# hermes-control.net
KiCad netlist of a schematic drawn in EAGLE
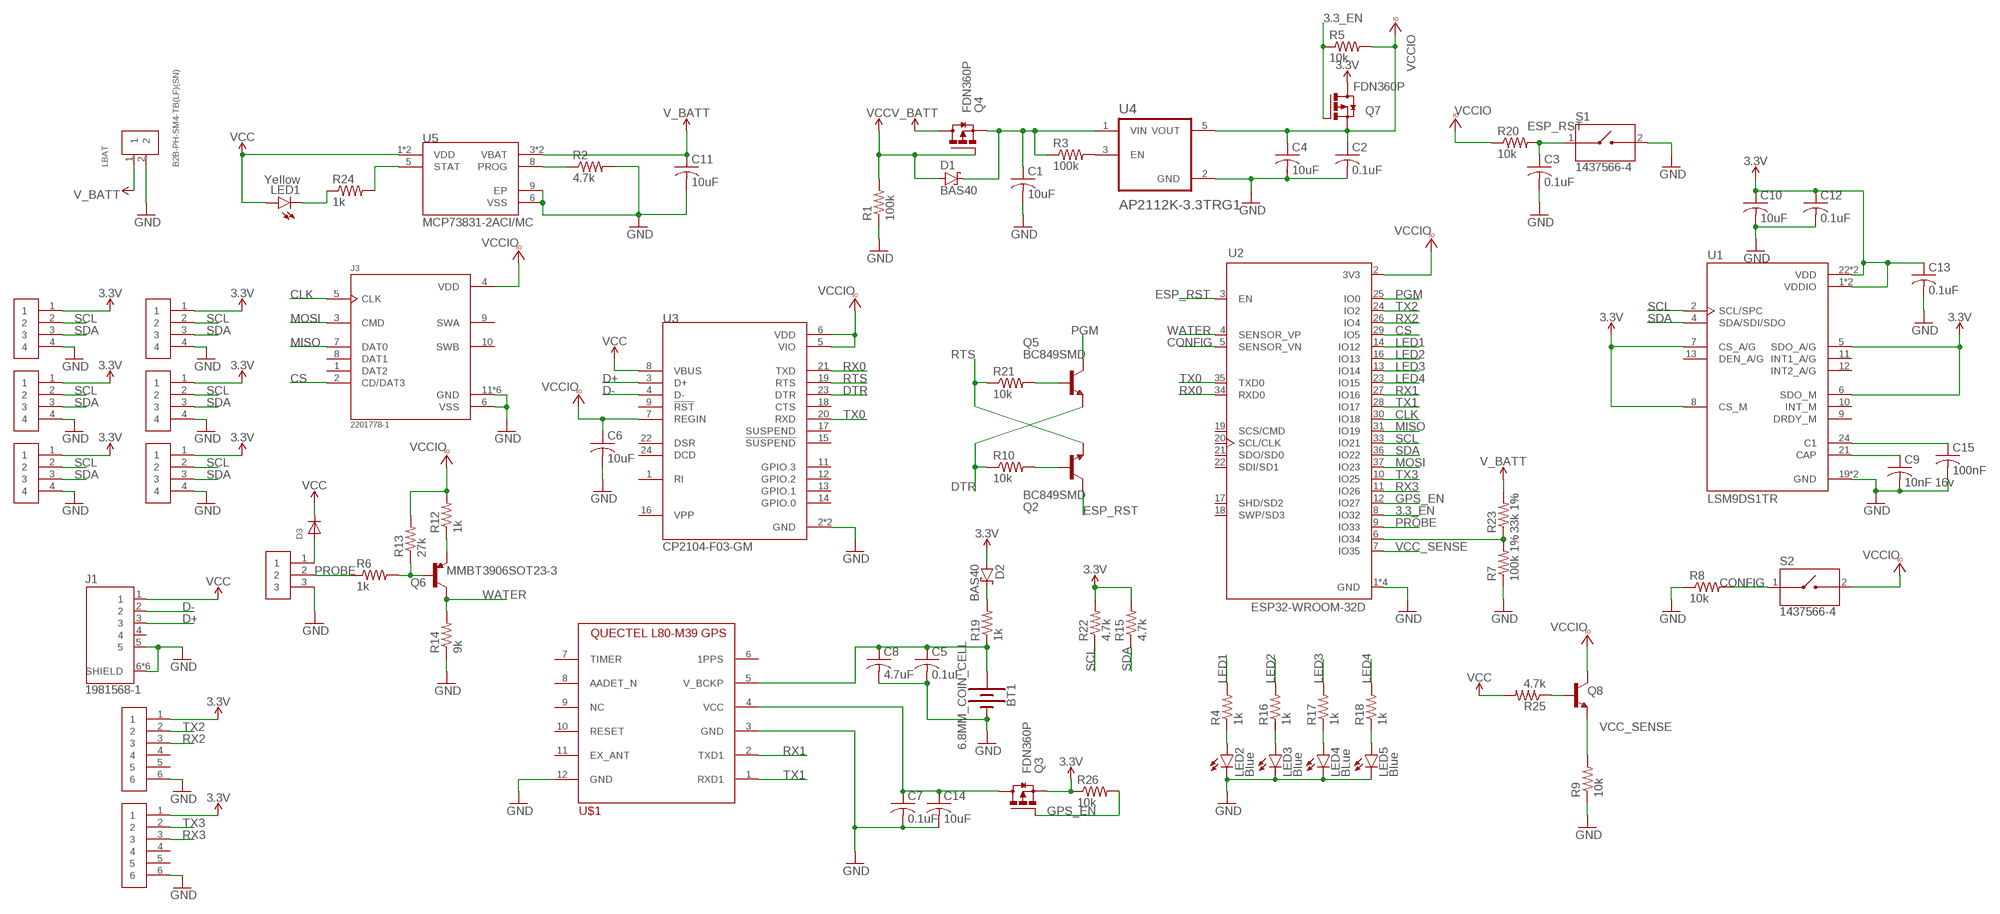
[diagram p0: schematic, sheet 1]

(export (version "E")
  (design (tool "Eeschema 10.0.6"))
  (components
    (comp (ref "BT1")
      (value "6.8MM_COIN_CELL")
      (footprint "eagle-import:BATTCON-6.8MM")
      (libsource (lib "eagle-import") (part "BATTERY-6.8MM_SMD"))
    )
    (comp (ref "C1")
      (value "10uF")
      (footprint "eagle-import:C0603")
      (libsource (lib "eagle-import") (part "C-USC0603"))
    )
    (comp (ref "C2")
      (value "0.1uF")
      (footprint "eagle-import:C0603")
      (libsource (lib "eagle-import") (part "C-USC0603"))
    )
    (comp (ref "C3")
      (value "0.1uF")
      (footprint "eagle-import:C0603")
      (libsource (lib "eagle-import") (part "C-USC0603"))
    )
    (comp (ref "C4")
      (value "10uF")
      (footprint "eagle-import:C0603")
      (libsource (lib "eagle-import") (part "C-USC0603"))
    )
    (comp (ref "C5")
      (value "0.1uF")
      (footprint "eagle-import:C0603")
      (libsource (lib "eagle-import") (part "C-USC0603"))
    )
    (comp (ref "C6")
      (value "10uF")
      (footprint "eagle-import:C0603")
      (libsource (lib "eagle-import") (part "C-USC0603"))
    )
    (comp (ref "C7")
      (value "0.1uF")
      (footprint "eagle-import:C0603")
      (libsource (lib "eagle-import") (part "C-USC0603"))
    )
    (comp (ref "C8")
      (value "4.7uF")
      (footprint "eagle-import:C0603")
      (libsource (lib "eagle-import") (part "C-USC0603"))
    )
    (comp (ref "C9")
      (value "10nF 16v")
      (footprint "eagle-import:C0603")
      (libsource (lib "eagle-import") (part "C-USC0603"))
    )
    (comp (ref "C10")
      (value "10uF")
      (footprint "eagle-import:C0603")
      (libsource (lib "eagle-import") (part "C-USC0603"))
    )
    (comp (ref "C11")
      (value "10uF")
      (footprint "eagle-import:C0603")
      (libsource (lib "eagle-import") (part "C-USC0603"))
    )
    (comp (ref "C12")
      (value "0.1uF")
      (footprint "eagle-import:C0603")
      (libsource (lib "eagle-import") (part "C-USC0603"))
    )
    (comp (ref "C13")
      (value "0.1uF")
      (footprint "eagle-import:C0603")
      (libsource (lib "eagle-import") (part "C-USC0603"))
    )
    (comp (ref "C14")
      (value "10uF")
      (footprint "eagle-import:C0603")
      (libsource (lib "eagle-import") (part "C-USC0603"))
    )
    (comp (ref "C15")
      (value "100nF")
      (footprint "eagle-import:C0603")
      (libsource (lib "eagle-import") (part "C-USC0603"))
    )
    (comp (ref "D1")
      (value "BAS40")
      (footprint "eagle-import:SOT23")
      (libsource (lib "eagle-import") (part "BAS40"))
    )
    (comp (ref "D2")
      (value "BAS40")
      (footprint "eagle-import:SOT23")
      (libsource (lib "eagle-import") (part "BAS40"))
    )
    (comp (ref "D3")
      (value "DIODE_SOD-123FL")
      (footprint "eagle-import:SOD-123FL")
      (libsource (lib "eagle-import") (part "DIODE_SOD-123FL"))
    )
    (comp (ref "J1")
      (value "1981568-1")
      (footprint "eagle-import:TE_1981568-1")
      (fields (field (name "MANUFACTURER") "TE CONNECTIVITY") (field (name "TE_PART_NUMBER") "1981568-1 "))
      (libsource (lib "eagle-import") (part "1981568-1"))
    )
    (comp (ref "J3")
      (value "2201778-1")
      (footprint "eagle-import:TE_2201778-1")
      (fields (field (name "MANUFACTURER") "TE Connectivity"))
      (libsource (lib "eagle-import") (part "2201778-1"))
    )
    (comp (ref "LBAT")
      (value "B2B-PH-SM4-TB(LF)(SN)")
      (footprint "eagle-import:JST_B2B-PH-SM4-TB(LF)(SN)")
      (fields (field (name "MF") "JST Sales") (field (name "MP") "B2B-PH-SM4-TB_LF__SN_"))
      (libsource (lib "eagle-import") (part "B2B-PH-SM4-TB(LF)(SN)"))
    )
    (comp (ref "LED1")
      (value "Yellow")
      (footprint "eagle-import:CHIPLED_0805")
      (libsource (lib "eagle-import") (part "LEDCHIPLED_0805"))
    )
    (comp (ref "LED2")
      (value "Blue")
      (footprint "eagle-import:CHIPLED_0805")
      (libsource (lib "eagle-import") (part "LEDCHIPLED_0805"))
    )
    (comp (ref "LED3")
      (value "Blue")
      (footprint "eagle-import:CHIPLED_0805")
      (libsource (lib "eagle-import") (part "LEDCHIPLED_0805"))
    )
    (comp (ref "LED4")
      (value "BLue")
      (footprint "eagle-import:CHIPLED_0805")
      (libsource (lib "eagle-import") (part "LEDCHIPLED_0805"))
    )
    (comp (ref "LED5")
      (value "Blue")
      (footprint "eagle-import:CHIPLED_0805")
      (libsource (lib "eagle-import") (part "LEDCHIPLED_0805"))
    )
    (comp (ref "Q2")
      (value "BC849SMD")
      (footprint "eagle-import:SOT23-BEC")
      (libsource (lib "eagle-import") (part "BC849SMD"))
    )
    (comp (ref "Q3")
      (value "FDN360P")
      (footprint "eagle-import:SUPER-SOT3")
      (libsource (lib "eagle-import") (part "FDN360P"))
    )
    (comp (ref "Q4")
      (value "FDN360P")
      (footprint "eagle-import:SUPER-SOT3")
      (libsource (lib "eagle-import") (part "FDN360P"))
    )
    (comp (ref "Q5")
      (value "BC849SMD")
      (footprint "eagle-import:SOT23-BEC")
      (libsource (lib "eagle-import") (part "BC849SMD"))
    )
    (comp (ref "Q6")
      (value "MMBT3906SOT23-3")
      (footprint "eagle-import:SOT23-3")
      (fields (field (name "MF") "STMicroelectronics") (field (name "MP") "MMBT3906"))
      (libsource (lib "eagle-import") (part "MMBT3906SOT23-3"))
    )
    (comp (ref "Q7")
      (value "FDN360P")
      (footprint "eagle-import:SUPER-SOT3")
      (libsource (lib "eagle-import") (part "FDN360P"))
    )
    (comp (ref "Q8")
      (value "MMBT2222A")
      (footprint "eagle-import:SOT23")
      (libsource (lib "eagle-import") (part "MMBT2222A"))
    )
    (comp (ref "R1")
      (value "100k")
      (footprint "eagle-import:R0603")
      (libsource (lib "eagle-import") (part "R-US_R0603"))
    )
    (comp (ref "R2")
      (value "4.7k")
      (footprint "eagle-import:R0603")
      (libsource (lib "eagle-import") (part "R-US_R0603"))
    )
    (comp (ref "R3")
      (value "100k")
      (footprint "eagle-import:R0603")
      (libsource (lib "eagle-import") (part "R-US_R0603"))
    )
    (comp (ref "R4")
      (value "1k")
      (footprint "eagle-import:R0603")
      (libsource (lib "eagle-import") (part "R-US_R0603"))
    )
    (comp (ref "R5")
      (value "10k")
      (footprint "eagle-import:R0603")
      (libsource (lib "eagle-import") (part "R-US_R0603"))
    )
    (comp (ref "R6")
      (value "1k")
      (footprint "eagle-import:R0603")
      (libsource (lib "eagle-import") (part "R-US_R0603"))
    )
    (comp (ref "R7")
      (value "100k 1%")
      (footprint "eagle-import:R0603")
      (libsource (lib "eagle-import") (part "R-US_R0603"))
    )
    (comp (ref "R8")
      (value "10k")
      (footprint "eagle-import:R0603")
      (libsource (lib "eagle-import") (part "R-US_R0603"))
    )
    (comp (ref "R9")
      (value "10k")
      (footprint "eagle-import:R0603")
      (libsource (lib "eagle-import") (part "R-US_R0603"))
    )
    (comp (ref "R10")
      (value "10k")
      (footprint "eagle-import:R0603")
      (libsource (lib "eagle-import") (part "R-US_R0603"))
    )
    (comp (ref "R12")
      (value "1k")
      (footprint "eagle-import:R0603")
      (libsource (lib "eagle-import") (part "R-US_R0603"))
    )
    (comp (ref "R13")
      (value "27k")
      (footprint "eagle-import:R0603")
      (libsource (lib "eagle-import") (part "R-US_R0603"))
    )
    (comp (ref "R14")
      (value "9k")
      (footprint "eagle-import:R0603")
      (libsource (lib "eagle-import") (part "R-US_R0603"))
    )
    (comp (ref "R15")
      (value "4.7k")
      (footprint "eagle-import:R0603")
      (libsource (lib "eagle-import") (part "R-US_R0603"))
    )
    (comp (ref "R16")
      (value "1k")
      (footprint "eagle-import:R0603")
      (libsource (lib "eagle-import") (part "R-US_R0603"))
    )
    (comp (ref "R17")
      (value "1k")
      (footprint "eagle-import:R0603")
      (libsource (lib "eagle-import") (part "R-US_R0603"))
    )
    (comp (ref "R18")
      (value "1k")
      (footprint "eagle-import:R0603")
      (libsource (lib "eagle-import") (part "R-US_R0603"))
    )
    (comp (ref "R19")
      (value "1k")
      (footprint "eagle-import:R0603")
      (libsource (lib "eagle-import") (part "R-US_R0603"))
    )
    (comp (ref "R20")
      (value "10k")
      (footprint "eagle-import:R0603")
      (libsource (lib "eagle-import") (part "R-US_R0603"))
    )
    (comp (ref "R21")
      (value "10k")
      (footprint "eagle-import:R0603")
      (libsource (lib "eagle-import") (part "R-US_R0603"))
    )
    (comp (ref "R22")
      (value "4.7k")
      (footprint "eagle-import:R0603")
      (libsource (lib "eagle-import") (part "R-US_R0603"))
    )
    (comp (ref "R23")
      (value "33k 1%")
      (footprint "eagle-import:R0603")
      (libsource (lib "eagle-import") (part "R-US_R0603"))
    )
    (comp (ref "R24")
      (value "1k")
      (footprint "eagle-import:R0603")
      (libsource (lib "eagle-import") (part "R-US_R0603"))
    )
    (comp (ref "R25")
      (value "4.7k")
      (footprint "eagle-import:R0603")
      (libsource (lib "eagle-import") (part "R-US_R0603"))
    )
    (comp (ref "R26")
      (value "10k")
      (footprint "eagle-import:R0603")
      (libsource (lib "eagle-import") (part "R-US_R0603"))
    )
    (comp (ref "S1")
      (value "1437566-4")
      (footprint "eagle-import:SW_1437566-4")
      (fields (field (name "MF") "TE Connectivity") (field (name "MP") "FSMSMTR"))
      (libsource (lib "eagle-import") (part "1437566-4"))
    )
    (comp (ref "S2")
      (value "1437566-4")
      (footprint "eagle-import:SW_1437566-4")
      (fields (field (name "MF") "TE Connectivity") (field (name "MP") "FSMSMTR"))
      (libsource (lib "eagle-import") (part "1437566-4"))
    )
    (comp (ref "U$1")
      (value "L80_GNSS_MODULE")
      (footprint "eagle-import:L80_PACKAGE")
      (libsource (lib "eagle-import") (part "L80_GNSS_MODULE"))
    )
    (comp (ref "U$2")
      (value "JST-GH-3VERT")
      (footprint "eagle-import:JST-GH-TOP-3")
      (libsource (lib "eagle-import") (part "JST-GH-3VERT"))
    )
    (comp (ref "U$3")
      (value "JST-GH-4TOP")
      (footprint "eagle-import:JST-GH-TOP-4")
      (libsource (lib "eagle-import") (part "JST-GH-4TOP"))
    )
    (comp (ref "U$4")
      (value "JST-GH-4TOP")
      (footprint "eagle-import:JST-GH-TOP-4")
      (libsource (lib "eagle-import") (part "JST-GH-4TOP"))
    )
    (comp (ref "U$5")
      (value "JST-GH-4TOP")
      (footprint "eagle-import:JST-GH-TOP-4")
      (libsource (lib "eagle-import") (part "JST-GH-4TOP"))
    )
    (comp (ref "U$7")
      (value "JST-GH-6TOP-ENTRY")
      (footprint "eagle-import:JST-GH-TOP-6")
      (libsource (lib "eagle-import") (part "JST-GH-6TOP-ENTRY"))
    )
    (comp (ref "U$8")
      (value "JST-GH-6TOP-ENTRY")
      (footprint "eagle-import:JST-GH-TOP-6")
      (libsource (lib "eagle-import") (part "JST-GH-6TOP-ENTRY"))
    )
    (comp (ref "U$9")
      (value "JST-GH-4TOP")
      (footprint "eagle-import:JST-GH-TOP-4")
      (libsource (lib "eagle-import") (part "JST-GH-4TOP"))
    )
    (comp (ref "U$10")
      (value "JST-GH-4TOP")
      (footprint "eagle-import:JST-GH-TOP-4")
      (libsource (lib "eagle-import") (part "JST-GH-4TOP"))
    )
    (comp (ref "U$11")
      (value "JST-GH-4TOP")
      (footprint "eagle-import:JST-GH-TOP-4")
      (libsource (lib "eagle-import") (part "JST-GH-4TOP"))
    )
    (comp (ref "U1")
      (value "LSM9DS1TR")
      (footprint "eagle-import:PQFN43P300X350X102-24N")
      (fields (field (name "MANUFACTURER") "ST MICROELECTRONICS"))
      (libsource (lib "eagle-import") (part "LSM9DS1TR"))
    )
    (comp (ref "U2")
      (value "ESP32-WROOM-32D")
      (footprint "eagle-import:MODULE_ESP32-WROOM-32D")
      (fields (field (name "MANUFACTURER") "Espressif Systems"))
      (libsource (lib "eagle-import") (part "ESP32-WROOM-32D"))
    )
    (comp (ref "U3")
      (value "CP2104-F03-GM")
      (footprint "eagle-import:QFN50P400X400X80-25N")
      (fields (field (name "MANUFACTURER") "Silicon Labs"))
      (libsource (lib "eagle-import") (part "CP2104-F03-GM"))
    )
    (comp (ref "U4")
      (value "AP2112K-3.3TRG1")
      (footprint "eagle-import:SOT95P285X140-5N")
      (fields (field (name "MANUFACTURER") "Diodes Inc."))
      (libsource (lib "eagle-import") (part "AP2112K-3.3TRG1"))
    )
    (comp (ref "U5")
      (value "MCP73831-2ACI/MC")
      (footprint "eagle-import:SON50P200X300X100-9N")
      (fields (field (name "MANUFACTURER") "MICROCHIP"))
      (libsource (lib "eagle-import") (part "MCP73831-2ACI/MC"))
    )
  )
  (nets
    (net (code "1") (name "/3.3_EN") (class "Default")
      (node (ref "Q7") (pin "1") (pinfunction "G_1") (pintype "passive"))
      (node (ref "R5") (pin "1") (pinfunction "1_1") (pintype "passive"))
      (node (ref "U2") (pin "8") (pinfunction "IO32_8") (pintype "bidirectional"))
    )
    (net (code "2") (name "/CLK") (class "Default")
      (node (ref "J3") (pin "5") (pinfunction "CLK_5") (pintype "input"))
      (node (ref "U2") (pin "30") (pinfunction "IO18_30") (pintype "bidirectional"))
    )
    (net (code "3") (name "/CONFIG") (class "Default")
      (node (ref "R8") (pin "2") (pinfunction "2_2") (pintype "passive"))
      (node (ref "S2") (pin "1") (pinfunction "1_1") (pintype "passive"))
      (node (ref "U2") (pin "5") (pinfunction "SENSOR_VN_5") (pintype "input"))
    )
    (net (code "4") (name "/CS") (class "Default")
      (node (ref "J3") (pin "2") (pinfunction "CD/DAT3_2") (pintype "bidirectional"))
      (node (ref "U2") (pin "29") (pinfunction "IO5_29") (pintype "bidirectional"))
    )
    (net (code "5") (name "/D+") (class "Default")
      (node (ref "J1") (pin "3") (pinfunction "3_3") (pintype "passive"))
      (node (ref "U3") (pin "3") (pinfunction "D+_3") (pintype "bidirectional"))
    )
    (net (code "6") (name "/D-") (class "Default")
      (node (ref "J1") (pin "2") (pinfunction "2_2") (pintype "passive"))
      (node (ref "U3") (pin "4") (pinfunction "D-_4") (pintype "bidirectional"))
    )
    (net (code "7") (name "/DTR") (class "Default")
      (node (ref "Q5") (pin "E") (pinfunction "E_E") (pintype "passive"))
      (node (ref "R10") (pin "1") (pinfunction "1_1") (pintype "passive"))
      (node (ref "U3") (pin "23") (pinfunction "DTR_23") (pintype "output"))
    )
    (net (code "8") (name "/ESP_RST") (class "Default")
      (node (ref "C3") (pin "1") (pinfunction "1_1") (pintype "passive"))
      (node (ref "Q2") (pin "C") (pinfunction "C_C") (pintype "passive"))
      (node (ref "R20") (pin "2") (pinfunction "2_2") (pintype "passive"))
      (node (ref "S1") (pin "1") (pinfunction "1_1") (pintype "passive"))
      (node (ref "U2") (pin "3") (pinfunction "EN_3") (pintype "input"))
    )
    (net (code "9") (name "/GPS_EN") (class "Default")
      (node (ref "Q3") (pin "1") (pinfunction "G_1") (pintype "passive"))
      (node (ref "R26") (pin "2") (pinfunction "2_2") (pintype "passive"))
      (node (ref "U2") (pin "12") (pinfunction "IO27_12") (pintype "bidirectional"))
    )
    (net (code "10") (name "/LED1") (class "Default")
      (node (ref "R4") (pin "2") (pinfunction "2_2") (pintype "passive"))
      (node (ref "U2") (pin "14") (pinfunction "IO12_14") (pintype "bidirectional"))
    )
    (net (code "11") (name "/LED2") (class "Default")
      (node (ref "R16") (pin "2") (pinfunction "2_2") (pintype "passive"))
      (node (ref "U2") (pin "16") (pinfunction "IO13_16") (pintype "bidirectional"))
    )
    (net (code "12") (name "/LED3") (class "Default")
      (node (ref "R17") (pin "2") (pinfunction "2_2") (pintype "passive"))
      (node (ref "U2") (pin "13") (pinfunction "IO14_13") (pintype "bidirectional"))
    )
    (net (code "13") (name "/LED4") (class "Default")
      (node (ref "R18") (pin "2") (pinfunction "2_2") (pintype "passive"))
      (node (ref "U2") (pin "23") (pinfunction "IO15_23") (pintype "bidirectional"))
    )
    (net (code "14") (name "/MISO") (class "Default")
      (node (ref "J3") (pin "7") (pinfunction "DAT0_7") (pintype "bidirectional"))
      (node (ref "U2") (pin "31") (pinfunction "IO19_31") (pintype "bidirectional"))
    )
    (net (code "15") (name "/MOSI") (class "Default")
      (node (ref "J3") (pin "3") (pinfunction "CMD_3") (pintype "bidirectional"))
      (node (ref "U2") (pin "37") (pinfunction "IO23_37") (pintype "bidirectional"))
    )
    (net (code "16") (name "/PGM") (class "Default")
      (node (ref "Q5") (pin "C") (pinfunction "C_C") (pintype "passive"))
      (node (ref "U2") (pin "25") (pinfunction "IO0_25") (pintype "bidirectional"))
    )
    (net (code "17") (name "/PROBE") (class "Default")
      (node (ref "R6") (pin "1") (pinfunction "1_1") (pintype "passive"))
      (node (ref "U$2") (pin "2") (pinfunction "2_2") (pintype "bidirectional"))
      (node (ref "U2") (pin "9") (pinfunction "IO33_9") (pintype "bidirectional"))
    )
    (net (code "18") (name "/RTS") (class "Default")
      (node (ref "Q2") (pin "E") (pinfunction "E_E") (pintype "passive"))
      (node (ref "R21") (pin "1") (pinfunction "1_1") (pintype "passive"))
      (node (ref "U3") (pin "19") (pinfunction "RTS_19") (pintype "output"))
    )
    (net (code "19") (name "/RX0") (class "Default")
      (node (ref "U2") (pin "34") (pinfunction "RXD0_34") (pintype "bidirectional"))
      (node (ref "U3") (pin "21") (pinfunction "TXD_21") (pintype "output"))
    )
    (net (code "20") (name "/RX1") (class "Default")
      (node (ref "U$1") (pin "2") (pinfunction "TXD1_2") (pintype "bidirectional"))
      (node (ref "U2") (pin "27") (pinfunction "IO16_27") (pintype "bidirectional"))
    )
    (net (code "21") (name "/RX2") (class "Default")
      (node (ref "U$7") (pin "3") (pinfunction "3_3") (pintype "bidirectional"))
      (node (ref "U2") (pin "26") (pinfunction "IO4_26") (pintype "bidirectional"))
    )
    (net (code "22") (name "/RX3") (class "Default")
      (node (ref "U$8") (pin "3") (pinfunction "3_3") (pintype "bidirectional"))
      (node (ref "U2") (pin "11") (pinfunction "IO26_11") (pintype "bidirectional"))
    )
    (net (code "23") (name "/SCL") (class "Default")
      (node (ref "R22") (pin "1") (pinfunction "1_1") (pintype "passive"))
      (node (ref "U$10") (pin "2") (pinfunction "2_2") (pintype "bidirectional"))
      (node (ref "U$11") (pin "2") (pinfunction "2_2") (pintype "bidirectional"))
      (node (ref "U$3") (pin "2") (pinfunction "2_2") (pintype "bidirectional"))
      (node (ref "U$4") (pin "2") (pinfunction "2_2") (pintype "bidirectional"))
      (node (ref "U$5") (pin "2") (pinfunction "2_2") (pintype "bidirectional"))
      (node (ref "U$9") (pin "2") (pinfunction "2_2") (pintype "bidirectional"))
      (node (ref "U1") (pin "2") (pinfunction "SCL/SPC_2") (pintype "input"))
      (node (ref "U2") (pin "33") (pinfunction "IO21_33") (pintype "bidirectional"))
    )
    (net (code "24") (name "/SDA") (class "Default")
      (node (ref "R15") (pin "1") (pinfunction "1_1") (pintype "passive"))
      (node (ref "U$10") (pin "3") (pinfunction "3_3") (pintype "bidirectional"))
      (node (ref "U$11") (pin "3") (pinfunction "3_3") (pintype "bidirectional"))
      (node (ref "U$3") (pin "3") (pinfunction "3_3") (pintype "bidirectional"))
      (node (ref "U$4") (pin "3") (pinfunction "3_3") (pintype "bidirectional"))
      (node (ref "U$5") (pin "3") (pinfunction "3_3") (pintype "bidirectional"))
      (node (ref "U$9") (pin "3") (pinfunction "3_3") (pintype "bidirectional"))
      (node (ref "U1") (pin "4") (pinfunction "SDA/SDI/SDO_4") (pintype "bidirectional"))
      (node (ref "U2") (pin "36") (pinfunction "IO22_36") (pintype "bidirectional"))
    )
    (net (code "25") (name "/TX0") (class "Default")
      (node (ref "U2") (pin "35") (pinfunction "TXD0_35") (pintype "bidirectional"))
      (node (ref "U3") (pin "20") (pinfunction "RXD_20") (pintype "input"))
    )
    (net (code "26") (name "/TX1") (class "Default")
      (node (ref "U$1") (pin "1") (pinfunction "RXD1_1") (pintype "bidirectional"))
      (node (ref "U2") (pin "28") (pinfunction "IO17_28") (pintype "bidirectional"))
    )
    (net (code "27") (name "/TX2") (class "Default")
      (node (ref "U$7") (pin "2") (pinfunction "2_2") (pintype "bidirectional"))
      (node (ref "U2") (pin "24") (pinfunction "IO2_24") (pintype "bidirectional"))
    )
    (net (code "28") (name "/TX3") (class "Default")
      (node (ref "U$8") (pin "2") (pinfunction "2_2") (pintype "bidirectional"))
      (node (ref "U2") (pin "10") (pinfunction "IO25_10") (pintype "bidirectional"))
    )
    (net (code "29") (name "/VCC_SENSE") (class "Default")
      (node (ref "Q8") (pin "2") (pinfunction "E_2") (pintype "passive"))
      (node (ref "R9") (pin "2") (pinfunction "2_2") (pintype "passive"))
      (node (ref "U2") (pin "7") (pinfunction "IO35_7") (pintype "bidirectional"))
    )
    (net (code "30") (name "/WATER") (class "Default")
      (node (ref "Q6") (pin "3") (pinfunction "C_3") (pintype "passive"))
      (node (ref "R14") (pin "2") (pinfunction "2_2") (pintype "passive"))
      (node (ref "U2") (pin "4") (pinfunction "SENSOR_VP_4") (pintype "input"))
    )
    (net (code "31") (name "3.3V") (class "Default")
      (node (ref "C10") (pin "1") (pinfunction "1_1") (pintype "passive"))
      (node (ref "C12") (pin "1") (pinfunction "1_1") (pintype "passive"))
      (node (ref "C13") (pin "1") (pinfunction "1_1") (pintype "passive"))
      (node (ref "D2") (pin "1") (pinfunction "A_1") (pintype "passive"))
      (node (ref "Q3") (pin "2") (pinfunction "S_2") (pintype "passive"))
      (node (ref "Q7") (pin "3") (pinfunction "D_3") (pintype "passive"))
      (node (ref "R15") (pin "2") (pinfunction "2_2") (pintype "passive"))
      (node (ref "R22") (pin "2") (pinfunction "2_2") (pintype "passive"))
      (node (ref "R26") (pin "1") (pinfunction "1_1") (pintype "passive"))
      (node (ref "U$10") (pin "1") (pinfunction "1_1") (pintype "bidirectional"))
      (node (ref "U$11") (pin "1") (pinfunction "1_1") (pintype "bidirectional"))
      (node (ref "U$3") (pin "1") (pinfunction "1_1") (pintype "bidirectional"))
      (node (ref "U$4") (pin "1") (pinfunction "1_1") (pintype "bidirectional"))
      (node (ref "U$5") (pin "1") (pinfunction "1_1") (pintype "bidirectional"))
      (node (ref "U$7") (pin "1") (pinfunction "1_1") (pintype "bidirectional"))
      (node (ref "U$8") (pin "1") (pinfunction "1_1") (pintype "bidirectional"))
      (node (ref "U$9") (pin "1") (pinfunction "1_1") (pintype "bidirectional"))
      (node (ref "U1") (pin "1") (pinfunction "VDDIO_1") (pintype "power_in"))
      (node (ref "U1") (pin "22") (pinfunction "VDD_22") (pintype "power_in"))
      (node (ref "U1") (pin "23") (pinfunction "VDD_23") (pintype "power_in"))
      (node (ref "U1") (pin "3") (pinfunction "VDDIO_3") (pintype "power_in"))
      (node (ref "U1") (pin "5") (pinfunction "SDO_A/G_5") (pintype "output"))
      (node (ref "U1") (pin "6") (pinfunction "SDO_M_6") (pintype "output"))
      (node (ref "U1") (pin "7") (pinfunction "CS_A/G_7") (pintype "input"))
      (node (ref "U1") (pin "8") (pinfunction "CS_M_8") (pintype "input"))
    )
    (net (code "32") (name "GND") (class "Default")
      (node (ref "BT1") (pin "-") (pinfunction "-_-") (pintype "power_in"))
      (node (ref "C1") (pin "2") (pinfunction "2_2") (pintype "passive"))
      (node (ref "C10") (pin "2") (pinfunction "2_2") (pintype "passive"))
      (node (ref "C11") (pin "2") (pinfunction "2_2") (pintype "passive"))
      (node (ref "C12") (pin "2") (pinfunction "2_2") (pintype "passive"))
      (node (ref "C13") (pin "2") (pinfunction "2_2") (pintype "passive"))
      (node (ref "C14") (pin "2") (pinfunction "2_2") (pintype "passive"))
      (node (ref "C15") (pin "2") (pinfunction "2_2") (pintype "passive"))
      (node (ref "C2") (pin "2") (pinfunction "2_2") (pintype "passive"))
      (node (ref "C3") (pin "2") (pinfunction "2_2") (pintype "passive"))
      (node (ref "C4") (pin "2") (pinfunction "2_2") (pintype "passive"))
      (node (ref "C5") (pin "2") (pinfunction "2_2") (pintype "passive"))
      (node (ref "C6") (pin "2") (pinfunction "2_2") (pintype "passive"))
      (node (ref "C7") (pin "2") (pinfunction "2_2") (pintype "passive"))
      (node (ref "C8") (pin "2") (pinfunction "2_2") (pintype "passive"))
      (node (ref "C9") (pin "2") (pinfunction "2_2") (pintype "passive"))
      (node (ref "J1") (pin "10") (pinfunction "SHIELD_10") (pintype "passive"))
      (node (ref "J1") (pin "11") (pinfunction "SHIELD_11") (pintype "passive"))
      (node (ref "J1") (pin "5") (pinfunction "5_5") (pintype "passive"))
      (node (ref "J1") (pin "6") (pinfunction "SHIELD_6") (pintype "passive"))
      (node (ref "J1") (pin "7") (pinfunction "SHIELD_7") (pintype "passive"))
      (node (ref "J1") (pin "8") (pinfunction "SHIELD_8") (pintype "passive"))
      (node (ref "J1") (pin "9") (pinfunction "SHIELD_9") (pintype "passive"))
      (node (ref "J3") (pin "11") (pinfunction "GND_11") (pintype "power_in"))
      (node (ref "J3") (pin "12") (pinfunction "GND_12") (pintype "power_in"))
      (node (ref "J3") (pin "13") (pinfunction "GND_13") (pintype "power_in"))
      (node (ref "J3") (pin "14") (pinfunction "GND_14") (pintype "power_in"))
      (node (ref "J3") (pin "15") (pinfunction "GND_15") (pintype "power_in"))
      (node (ref "J3") (pin "16") (pinfunction "GND_16") (pintype "power_in"))
      (node (ref "J3") (pin "6") (pinfunction "VSS_6") (pintype "power_in"))
      (node (ref "LBAT") (pin "2") (pinfunction "2_2") (pintype "passive"))
      (node (ref "LED2") (pin "C") (pinfunction "C_C") (pintype "passive"))
      (node (ref "LED3") (pin "C") (pinfunction "C_C") (pintype "passive"))
      (node (ref "LED4") (pin "C") (pinfunction "C_C") (pintype "passive"))
      (node (ref "LED5") (pin "C") (pinfunction "C_C") (pintype "passive"))
      (node (ref "R1") (pin "1") (pinfunction "1_1") (pintype "passive"))
      (node (ref "R14") (pin "1") (pinfunction "1_1") (pintype "passive"))
      (node (ref "R2") (pin "2") (pinfunction "2_2") (pintype "passive"))
      (node (ref "R7") (pin "1") (pinfunction "1_1") (pintype "passive"))
      (node (ref "R8") (pin "1") (pinfunction "1_1") (pintype "passive"))
      (node (ref "R9") (pin "1") (pinfunction "1_1") (pintype "passive"))
      (node (ref "S1") (pin "2") (pinfunction "2_2") (pintype "passive"))
      (node (ref "U$1") (pin "12") (pinfunction "GND_12") (pintype "bidirectional"))
      (node (ref "U$1") (pin "3") (pinfunction "GND_3") (pintype "bidirectional"))
      (node (ref "U$10") (pin "4") (pinfunction "4_4") (pintype "bidirectional"))
      (node (ref "U$11") (pin "4") (pinfunction "4_4") (pintype "bidirectional"))
      (node (ref "U$2") (pin "3") (pinfunction "3_3") (pintype "bidirectional"))
      (node (ref "U$3") (pin "4") (pinfunction "4_4") (pintype "bidirectional"))
      (node (ref "U$4") (pin "4") (pinfunction "4_4") (pintype "bidirectional"))
      (node (ref "U$5") (pin "4") (pinfunction "4_4") (pintype "bidirectional"))
      (node (ref "U$7") (pin "6") (pinfunction "6_6") (pintype "bidirectional"))
      (node (ref "U$8") (pin "6") (pinfunction "6_6") (pintype "bidirectional"))
      (node (ref "U$9") (pin "4") (pinfunction "4_4") (pintype "bidirectional"))
      (node (ref "U1") (pin "19") (pinfunction "GND_19") (pintype "power_in"))
      (node (ref "U1") (pin "20") (pinfunction "GND_20") (pintype "power_in"))
      (node (ref "U2") (pin "1") (pinfunction "GND_1") (pintype "power_in"))
      (node (ref "U2") (pin "15") (pinfunction "GND_15") (pintype "power_in"))
      (node (ref "U2") (pin "38") (pinfunction "GND_38") (pintype "power_in"))
      (node (ref "U2") (pin "39") (pinfunction "GND_39") (pintype "power_in"))
      (node (ref "U3") (pin "2") (pinfunction "GND_2") (pintype "power_in"))
      (node (ref "U3") (pin "25") (pinfunction "GND_25") (pintype "power_in"))
      (node (ref "U4") (pin "2") (pinfunction "GND_2") (pintype "power_in"))
      (node (ref "U5") (pin "6") (pinfunction "VSS_6") (pintype "power_in"))
      (node (ref "U5") (pin "9") (pinfunction "EP_9") (pintype "power_in"))
    )
    (net (code "33") (name "Net-(D1-C)") (class "Default")
      (node (ref "C1") (pin "1") (pinfunction "1_1") (pintype "passive"))
      (node (ref "D1") (pin "3") (pinfunction "C_3") (pintype "passive"))
      (node (ref "Q4") (pin "2") (pinfunction "S_2") (pintype "passive"))
      (node (ref "R3") (pin "1") (pinfunction "1_1") (pintype "passive"))
      (node (ref "U4") (pin "1") (pinfunction "VIN_1") (pintype "power_in"))
    )
    (net (code "34") (name "Net-(D2-C)") (class "Default")
      (node (ref "D2") (pin "3") (pinfunction "C_3") (pintype "passive"))
      (node (ref "R19") (pin "2") (pinfunction "2_2") (pintype "passive"))
    )
    (net (code "35") (name "Net-(D3-PadA)") (class "Default")
      (node (ref "D3") (pin "A") (pinfunction "A_A") (pintype "passive"))
      (node (ref "U$2") (pin "1") (pinfunction "1_1") (pintype "bidirectional"))
    )
    (net (code "36") (name "Net-(LED1-PadC)") (class "Default")
      (node (ref "LED1") (pin "C") (pinfunction "C_C") (pintype "passive"))
      (node (ref "R24") (pin "1") (pinfunction "1_1") (pintype "passive"))
    )
    (net (code "37") (name "Net-(LED2-PadA)") (class "Default")
      (node (ref "LED2") (pin "A") (pinfunction "A_A") (pintype "passive"))
      (node (ref "R4") (pin "1") (pinfunction "1_1") (pintype "passive"))
    )
    (net (code "38") (name "Net-(LED3-PadA)") (class "Default")
      (node (ref "LED3") (pin "A") (pinfunction "A_A") (pintype "passive"))
      (node (ref "R16") (pin "1") (pinfunction "1_1") (pintype "passive"))
    )
    (net (code "39") (name "Net-(LED4-PadA)") (class "Default")
      (node (ref "LED4") (pin "A") (pinfunction "A_A") (pintype "passive"))
      (node (ref "R17") (pin "1") (pinfunction "1_1") (pintype "passive"))
    )
    (net (code "40") (name "Net-(LED5-PadA)") (class "Default")
      (node (ref "LED5") (pin "A") (pinfunction "A_A") (pintype "passive"))
      (node (ref "R18") (pin "1") (pinfunction "1_1") (pintype "passive"))
    )
    (net (code "41") (name "Net-(Q2-PadB)") (class "Default")
      (node (ref "Q2") (pin "B") (pinfunction "B_B") (pintype "passive"))
      (node (ref "R10") (pin "2") (pinfunction "2_2") (pintype "passive"))
    )
    (net (code "42") (name "Net-(Q3-D)") (class "Default")
      (node (ref "C14") (pin "1") (pinfunction "1_1") (pintype "passive"))
      (node (ref "C7") (pin "1") (pinfunction "1_1") (pintype "passive"))
      (node (ref "Q3") (pin "3") (pinfunction "D_3") (pintype "passive"))
      (node (ref "U$1") (pin "4") (pinfunction "VCC_4") (pintype "bidirectional"))
    )
    (net (code "43") (name "Net-(Q5-PadB)") (class "Default")
      (node (ref "Q5") (pin "B") (pinfunction "B_B") (pintype "passive"))
      (node (ref "R21") (pin "2") (pinfunction "2_2") (pintype "passive"))
    )
    (net (code "44") (name "Net-(Q6-B)") (class "Default")
      (node (ref "Q6") (pin "1") (pinfunction "B_1") (pintype "passive"))
      (node (ref "R13") (pin "1") (pinfunction "1_1") (pintype "passive"))
      (node (ref "R6") (pin "2") (pinfunction "2_2") (pintype "passive"))
    )
    (net (code "45") (name "Net-(Q6-E)") (class "Default")
      (node (ref "Q6") (pin "2") (pinfunction "E_2") (pintype "passive"))
      (node (ref "R12") (pin "1") (pinfunction "1_1") (pintype "passive"))
    )
    (net (code "46") (name "Net-(Q8-B)") (class "Default")
      (node (ref "Q8") (pin "1") (pinfunction "B_1") (pintype "passive"))
      (node (ref "R25") (pin "1") (pinfunction "1_1") (pintype "passive"))
    )
    (net (code "47") (name "Net-(U$1-V_BCKP)") (class "Default")
      (node (ref "BT1") (pin "+") (pinfunction "+_+") (pintype "power_in"))
      (node (ref "C5") (pin "1") (pinfunction "1_1") (pintype "passive"))
      (node (ref "C8") (pin "1") (pinfunction "1_1") (pintype "passive"))
      (node (ref "R19") (pin "1") (pinfunction "1_1") (pintype "passive"))
      (node (ref "U$1") (pin "5") (pinfunction "V_BCKP_5") (pintype "bidirectional"))
    )
    (net (code "48") (name "Net-(U1-C1)") (class "Default")
      (node (ref "C15") (pin "1") (pinfunction "1_1") (pintype "passive"))
      (node (ref "U1") (pin "24") (pinfunction "C1_24") (pintype "passive"))
    )
    (net (code "49") (name "Net-(U1-CAP)") (class "Default")
      (node (ref "C9") (pin "1") (pinfunction "1_1") (pintype "passive"))
      (node (ref "U1") (pin "21") (pinfunction "CAP_21") (pintype "passive"))
    )
    (net (code "50") (name "Net-(U2-IO34)") (class "Default")
      (node (ref "R23") (pin "1") (pinfunction "1_1") (pintype "passive"))
      (node (ref "R7") (pin "2") (pinfunction "2_2") (pintype "passive"))
      (node (ref "U2") (pin "6") (pinfunction "IO34_6") (pintype "bidirectional"))
    )
    (net (code "51") (name "Net-(U4-EN)") (class "Default")
      (node (ref "R3") (pin "2") (pinfunction "2_2") (pintype "passive"))
      (node (ref "U4") (pin "3") (pinfunction "EN_3") (pintype "input"))
    )
    (net (code "52") (name "Net-(U5-PROG)") (class "Default")
      (node (ref "R2") (pin "1") (pinfunction "1_1") (pintype "passive"))
      (node (ref "U5") (pin "8") (pinfunction "PROG_8") (pintype "input"))
    )
    (net (code "53") (name "Net-(U5-STAT)") (class "Default")
      (node (ref "R24") (pin "2") (pinfunction "2_2") (pintype "passive"))
      (node (ref "U5") (pin "5") (pinfunction "STAT_5") (pintype "output"))
    )
    (net (code "54") (name "VCC") (class "Default")
      (node (ref "D1") (pin "1") (pinfunction "A_1") (pintype "passive"))
      (node (ref "D3") (pin "C") (pinfunction "C_C") (pintype "passive"))
      (node (ref "J1") (pin "1") (pinfunction "1_1") (pintype "passive"))
      (node (ref "LED1") (pin "A") (pinfunction "A_A") (pintype "passive"))
      (node (ref "Q4") (pin "1") (pinfunction "G_1") (pintype "passive"))
      (node (ref "R1") (pin "2") (pinfunction "2_2") (pintype "passive"))
      (node (ref "R25") (pin "2") (pinfunction "2_2") (pintype "passive"))
      (node (ref "U3") (pin "8") (pinfunction "VBUS_8") (pintype "input"))
      (node (ref "U5") (pin "1") (pinfunction "VDD_1") (pintype "power_in"))
      (node (ref "U5") (pin "2") (pinfunction "VDD_2") (pintype "power_in"))
    )
    (net (code "55") (name "VCCIO") (class "Default")
      (node (ref "C2") (pin "1") (pinfunction "1_1") (pintype "passive"))
      (node (ref "C4") (pin "1") (pinfunction "1_1") (pintype "passive"))
      (node (ref "C6") (pin "1") (pinfunction "1_1") (pintype "passive"))
      (node (ref "J3") (pin "4") (pinfunction "VDD_4") (pintype "power_in"))
      (node (ref "Q7") (pin "2") (pinfunction "S_2") (pintype "passive"))
      (node (ref "Q8") (pin "3") (pinfunction "C_3") (pintype "passive"))
      (node (ref "R12") (pin "2") (pinfunction "2_2") (pintype "passive"))
      (node (ref "R13") (pin "2") (pinfunction "2_2") (pintype "passive"))
      (node (ref "R20") (pin "1") (pinfunction "1_1") (pintype "passive"))
      (node (ref "R5") (pin "2") (pinfunction "2_2") (pintype "passive"))
      (node (ref "S2") (pin "2") (pinfunction "2_2") (pintype "passive"))
      (node (ref "U2") (pin "2") (pinfunction "3V3_2") (pintype "power_in"))
      (node (ref "U3") (pin "5") (pinfunction "VIO_5") (pintype "power_in"))
      (node (ref "U3") (pin "6") (pinfunction "VDD_6") (pintype "power_in"))
      (node (ref "U3") (pin "7") (pinfunction "REGIN_7") (pintype "input"))
      (node (ref "U4") (pin "5") (pinfunction "VOUT_5") (pintype "power_in"))
    )
    (net (code "56") (name "V_BATT") (class "Default")
      (node (ref "C11") (pin "1") (pinfunction "1_1") (pintype "passive"))
      (node (ref "LBAT") (pin "1") (pinfunction "1_1") (pintype "passive"))
      (node (ref "Q4") (pin "3") (pinfunction "D_3") (pintype "passive"))
      (node (ref "R23") (pin "2") (pinfunction "2_2") (pintype "passive"))
      (node (ref "U5") (pin "3") (pinfunction "VBAT_3") (pintype "output"))
      (node (ref "U5") (pin "4") (pinfunction "VBAT_4") (pintype "output"))
    )
    (net (code "57") (name "unconnected-(J1-Pad4)") (class "Default")
      (node (ref "J1") (pin "4") (pinfunction "4_4") (pintype "passive"))
    )
    (net (code "58") (name "unconnected-(J3-DAT1-Pad8)") (class "Default")
      (node (ref "J3") (pin "8") (pinfunction "DAT1_8") (pintype "bidirectional"))
    )
    (net (code "59") (name "unconnected-(J3-DAT2-Pad1)") (class "Default")
      (node (ref "J3") (pin "1") (pinfunction "DAT2_1") (pintype "bidirectional"))
    )
    (net (code "60") (name "unconnected-(J3-SWA-Pad9)") (class "Default")
      (node (ref "J3") (pin "9") (pinfunction "SWA_9") (pintype "passive"))
    )
    (net (code "61") (name "unconnected-(J3-SWB-Pad10)") (class "Default")
      (node (ref "J3") (pin "10") (pinfunction "SWB_10") (pintype "passive"))
    )
    (net (code "62") (name "unconnected-(U$1-1PPS-Pad6)") (class "Default")
      (node (ref "U$1") (pin "6") (pinfunction "1PPS_6") (pintype "bidirectional"))
    )
    (net (code "63") (name "unconnected-(U$1-AADET_N-Pad8)") (class "Default")
      (node (ref "U$1") (pin "8") (pinfunction "AADET_N_8") (pintype "bidirectional"))
    )
    (net (code "64") (name "unconnected-(U$1-EX_ANT-Pad11)") (class "Default")
      (node (ref "U$1") (pin "11") (pinfunction "EX_ANT_11") (pintype "bidirectional"))
    )
    (net (code "65") (name "unconnected-(U$1-NC-Pad9)") (class "Default")
      (node (ref "U$1") (pin "9") (pinfunction "NC_9") (pintype "bidirectional"))
    )
    (net (code "66") (name "unconnected-(U$1-RESET-Pad10)") (class "Default")
      (node (ref "U$1") (pin "10") (pinfunction "RESET_10") (pintype "bidirectional"))
    )
    (net (code "67") (name "unconnected-(U$1-TIMER-Pad7)") (class "Default")
      (node (ref "U$1") (pin "7") (pinfunction "TIMER_7") (pintype "bidirectional"))
    )
    (net (code "68") (name "unconnected-(U$7-Pad4)") (class "Default")
      (node (ref "U$7") (pin "4") (pinfunction "4_4") (pintype "bidirectional"))
    )
    (net (code "69") (name "unconnected-(U$7-Pad5)") (class "Default")
      (node (ref "U$7") (pin "5") (pinfunction "5_5") (pintype "bidirectional"))
    )
    (net (code "70") (name "unconnected-(U$8-Pad4)") (class "Default")
      (node (ref "U$8") (pin "4") (pinfunction "4_4") (pintype "bidirectional"))
    )
    (net (code "71") (name "unconnected-(U$8-Pad5)") (class "Default")
      (node (ref "U$8") (pin "5") (pinfunction "5_5") (pintype "bidirectional"))
    )
    (net (code "72") (name "unconnected-(U1-DEN_A{slash}G-Pad13)") (class "Default")
      (node (ref "U1") (pin "13") (pinfunction "DEN_A/G_13") (pintype "input"))
    )
    (net (code "73") (name "unconnected-(U1-DRDY_M-Pad9)") (class "Default")
      (node (ref "U1") (pin "9") (pinfunction "DRDY_M_9") (pintype "output"))
    )
    (net (code "74") (name "unconnected-(U1-INT1_A{slash}G-Pad11)") (class "Default")
      (node (ref "U1") (pin "11") (pinfunction "INT1_A/G_11") (pintype "output"))
    )
    (net (code "75") (name "unconnected-(U1-INT2_A{slash}G-Pad12)") (class "Default")
      (node (ref "U1") (pin "12") (pinfunction "INT2_A/G_12") (pintype "output"))
    )
    (net (code "76") (name "unconnected-(U1-INT_M-Pad10)") (class "Default")
      (node (ref "U1") (pin "10") (pinfunction "INT_M_10") (pintype "output"))
    )
    (net (code "77") (name "unconnected-(U2-SCL{slash}CLK-Pad20)") (class "Default")
      (node (ref "U2") (pin "20") (pinfunction "SCL/CLK_20") (pintype "bidirectional"))
    )
    (net (code "78") (name "unconnected-(U2-SCS{slash}CMD-Pad19)") (class "Default")
      (node (ref "U2") (pin "19") (pinfunction "SCS/CMD_19") (pintype "bidirectional"))
    )
    (net (code "79") (name "unconnected-(U2-SDI{slash}SD1-Pad22)") (class "Default")
      (node (ref "U2") (pin "22") (pinfunction "SDI/SD1_22") (pintype "bidirectional"))
    )
    (net (code "80") (name "unconnected-(U2-SDO{slash}SD0-Pad21)") (class "Default")
      (node (ref "U2") (pin "21") (pinfunction "SDO/SD0_21") (pintype "bidirectional"))
    )
    (net (code "81") (name "unconnected-(U2-SHD{slash}SD2-Pad17)") (class "Default")
      (node (ref "U2") (pin "17") (pinfunction "SHD/SD2_17") (pintype "bidirectional"))
    )
    (net (code "82") (name "unconnected-(U2-SWP{slash}SD3-Pad18)") (class "Default")
      (node (ref "U2") (pin "18") (pinfunction "SWP/SD3_18") (pintype "bidirectional"))
    )
    (net (code "83") (name "unconnected-(U3-CTS-Pad18)") (class "Default")
      (node (ref "U3") (pin "18") (pinfunction "CTS_18") (pintype "input"))
    )
    (net (code "84") (name "unconnected-(U3-DCD-Pad24)") (class "Default")
      (node (ref "U3") (pin "24") (pinfunction "DCD_24") (pintype "input"))
    )
    (net (code "85") (name "unconnected-(U3-DSR-Pad22)") (class "Default")
      (node (ref "U3") (pin "22") (pinfunction "DSR_22") (pintype "input"))
    )
    (net (code "86") (name "unconnected-(U3-GPIO.0-Pad14)") (class "Default")
      (node (ref "U3") (pin "14") (pinfunction "GPIO.0_14") (pintype "bidirectional"))
    )
    (net (code "87") (name "unconnected-(U3-GPIO.1-Pad13)") (class "Default")
      (node (ref "U3") (pin "13") (pinfunction "GPIO.1_13") (pintype "bidirectional"))
    )
    (net (code "88") (name "unconnected-(U3-GPIO.2-Pad12)") (class "Default")
      (node (ref "U3") (pin "12") (pinfunction "GPIO.2_12") (pintype "bidirectional"))
    )
    (net (code "89") (name "unconnected-(U3-GPIO.3-Pad11)") (class "Default")
      (node (ref "U3") (pin "11") (pinfunction "GPIO.3_11") (pintype "bidirectional"))
    )
    (net (code "90") (name "unconnected-(U3-RI-Pad1)") (class "Default")
      (node (ref "U3") (pin "1") (pinfunction "RI_1") (pintype "input"))
    )
    (net (code "91") (name "unconnected-(U3-SUSPEND-Pad17)") (class "Default")
      (node (ref "U3") (pin "17") (pinfunction "SUSPEND_17") (pintype "output"))
    )
    (net (code "92") (name "unconnected-(U3-VPP-Pad16)") (class "Default")
      (node (ref "U3") (pin "16") (pinfunction "VPP_16") (pintype "passive"))
    )
    (net (code "93") (name "unconnected-(U3-~{RST}-Pad9)") (class "Default")
      (node (ref "U3") (pin "9") (pinfunction "~{RST}_9") (pintype "input"))
    )
    (net (code "94") (name "unconnected-(U3-~{SUSPEND}-Pad15)") (class "Default")
      (node (ref "U3") (pin "15") (pinfunction "~{SUSPEND}_15") (pintype "output"))
    )
  )
)
